# CAN.net
KiCad netlist of a schematic drawn in Altium Designer
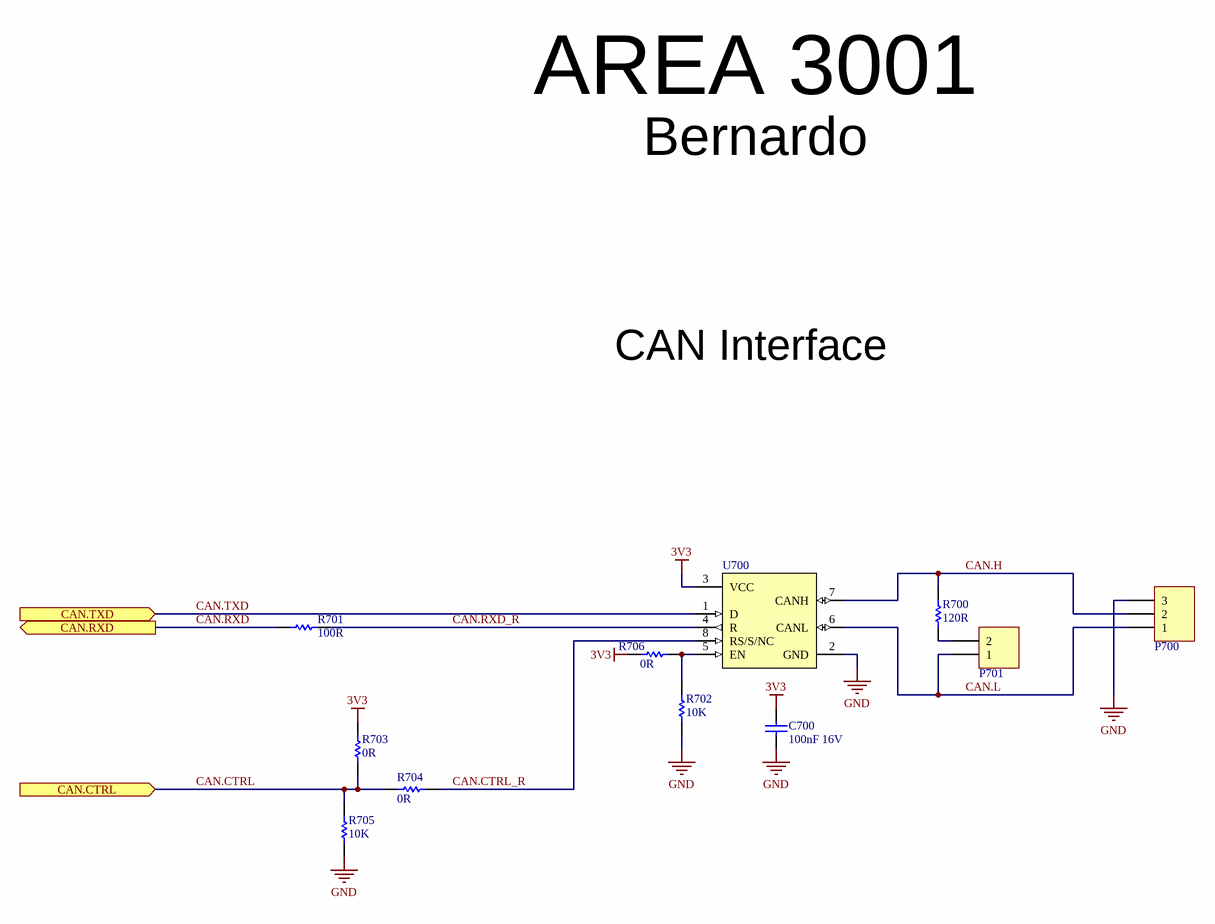
[diagram p0: CAN.SchDoc]

(export (version "E")
  (design (tool "Eeschema 10.0.6"))
  (components
    (comp (ref "C700")
      (value "100nF 16V")
      (footprint "C0603_N")
      (description "Capacitor Ceramic")
      (fields (field (name "Comment") "CAP_CERAMIC"))
      (libsource (lib "Phyx_Components") (part "CAP_CERAMIC"))
    )
    (comp (ref "P700")
      (value "3 Terminal Socket 2,5mm")
      (footprint "WE_691382000003")
      (libsource (lib "Phyx_Components") (part "Header 3"))
    )
    (comp (ref "P701")
      (value "Header 2")
      (footprint "HDR1X2")
      (libsource (lib "Phyx_Components") (part "Header 2"))
    )
    (comp (ref "R700")
      (value "120R")
      (footprint "R1206")
      (fields (field (name "Comment") "RESISTOR"))
      (libsource (lib "Phyx_Components") (part "RESISTOR"))
    )
    (comp (ref "R701")
      (value "100R")
      (footprint "R0603_N")
      (fields (field (name "Comment") "RESISTOR"))
      (libsource (lib "Phyx_Components") (part "RESISTOR"))
    )
    (comp (ref "R702")
      (value "10K")
      (footprint "R0603_N")
      (fields (field (name "Comment") "RESISTOR"))
      (libsource (lib "Phyx_Components") (part "RESISTOR"))
    )
    (comp (ref "R703")
      (value "0R")
      (footprint "R0603_N")
      (fields (field (name "Comment") "RESISTOR"))
      (libsource (lib "Phyx_Components") (part "RESISTOR"))
    )
    (comp (ref "R704")
      (value "0R")
      (footprint "R0603_N")
      (fields (field (name "Comment") "RESISTOR"))
      (libsource (lib "Phyx_Components") (part "RESISTOR"))
    )
    (comp (ref "R705")
      (value "10K")
      (footprint "R0603_N")
      (fields (field (name "Comment") "RESISTOR"))
      (libsource (lib "Phyx_Components") (part "RESISTOR"))
    )
    (comp (ref "R706")
      (value "0R")
      (footprint "R0603_N")
      (fields (field (name "Comment") "RESISTOR"))
      (libsource (lib "Phyx_Components") (part "RESISTOR"))
    )
    (comp (ref "U700")
      (value "CAN Transceiver 1Mbps 3V3")
      (footprint "SOIC_N_8")
      (description "=Description")
      (libsource (lib "Phyx_Components") (part "CAN_SO8"))
    )
  )
  (nets
    (net (code "1") (name "/CAN.CTRL") (class "Default")
      (node (ref "R703") (pin "2") (pinfunction "2_2") (pintype "passive"))
      (node (ref "R704") (pin "1") (pinfunction "1_1") (pintype "passive"))
      (node (ref "R705") (pin "1") (pinfunction "1_1") (pintype "passive"))
    )
    (net (code "2") (name "/CAN.CTRL_R") (class "Default")
      (node (ref "R704") (pin "2") (pinfunction "2_2") (pintype "passive"))
      (node (ref "U700") (pin "8") (pinfunction "RS/S/NC_8") (pintype "input"))
    )
    (net (code "3") (name "/CAN.H") (class "Default")
      (node (ref "P700") (pin "2") (pinfunction "2_2") (pintype "passive"))
      (node (ref "R700") (pin "1") (pinfunction "1_1") (pintype "passive"))
      (node (ref "U700") (pin "7") (pinfunction "CANH_7") (pintype "bidirectional"))
    )
    (net (code "4") (name "/CAN.L") (class "Default")
      (node (ref "P700") (pin "1") (pinfunction "1_1") (pintype "passive"))
      (node (ref "P701") (pin "1") (pinfunction "1_1") (pintype "passive"))
      (node (ref "U700") (pin "6") (pinfunction "CANL_6") (pintype "bidirectional"))
    )
    (net (code "5") (name "/CAN.RXD") (class "Default")
      (node (ref "R701") (pin "2") (pinfunction "2_2") (pintype "passive"))
    )
    (net (code "6") (name "/CAN.RXD_R") (class "Default")
      (node (ref "R701") (pin "1") (pinfunction "1_1") (pintype "passive"))
      (node (ref "U700") (pin "4") (pinfunction "R_4") (pintype "output"))
    )
    (net (code "7") (name "/CAN.TXD") (class "Default")
      (node (ref "U700") (pin "1") (pinfunction "D_1") (pintype "input"))
    )
    (net (code "8") (name "3V3") (class "Default")
      (node (ref "C700") (pin "1") (pinfunction "1_1") (pintype "passive"))
      (node (ref "R703") (pin "1") (pinfunction "1_1") (pintype "passive"))
      (node (ref "R706") (pin "1") (pinfunction "1_1") (pintype "passive"))
      (node (ref "U700") (pin "3") (pinfunction "VCC_3") (pintype "power_in"))
    )
    (net (code "9") (name "GND") (class "Default")
      (node (ref "C700") (pin "2") (pinfunction "2_2") (pintype "passive"))
      (node (ref "P700") (pin "3") (pinfunction "3_3") (pintype "passive"))
      (node (ref "R702") (pin "2") (pinfunction "2_2") (pintype "passive"))
      (node (ref "R705") (pin "2") (pinfunction "2_2") (pintype "passive"))
      (node (ref "U700") (pin "2") (pinfunction "GND_2") (pintype "power_in"))
    )
    (net (code "10") (name "Net-(P701-Pad2)") (class "Default")
      (node (ref "P701") (pin "2") (pinfunction "2_2") (pintype "passive"))
      (node (ref "R700") (pin "2") (pinfunction "2_2") (pintype "passive"))
    )
    (net (code "11") (name "Net-(U700-EN)") (class "Default")
      (node (ref "R702") (pin "1") (pinfunction "1_1") (pintype "passive"))
      (node (ref "R706") (pin "2") (pinfunction "2_2") (pintype "passive"))
      (node (ref "U700") (pin "5") (pinfunction "EN_5") (pintype "input"))
    )
  )
)
